# ssr.net
KiCad netlist of a schematic drawn in EAGLE
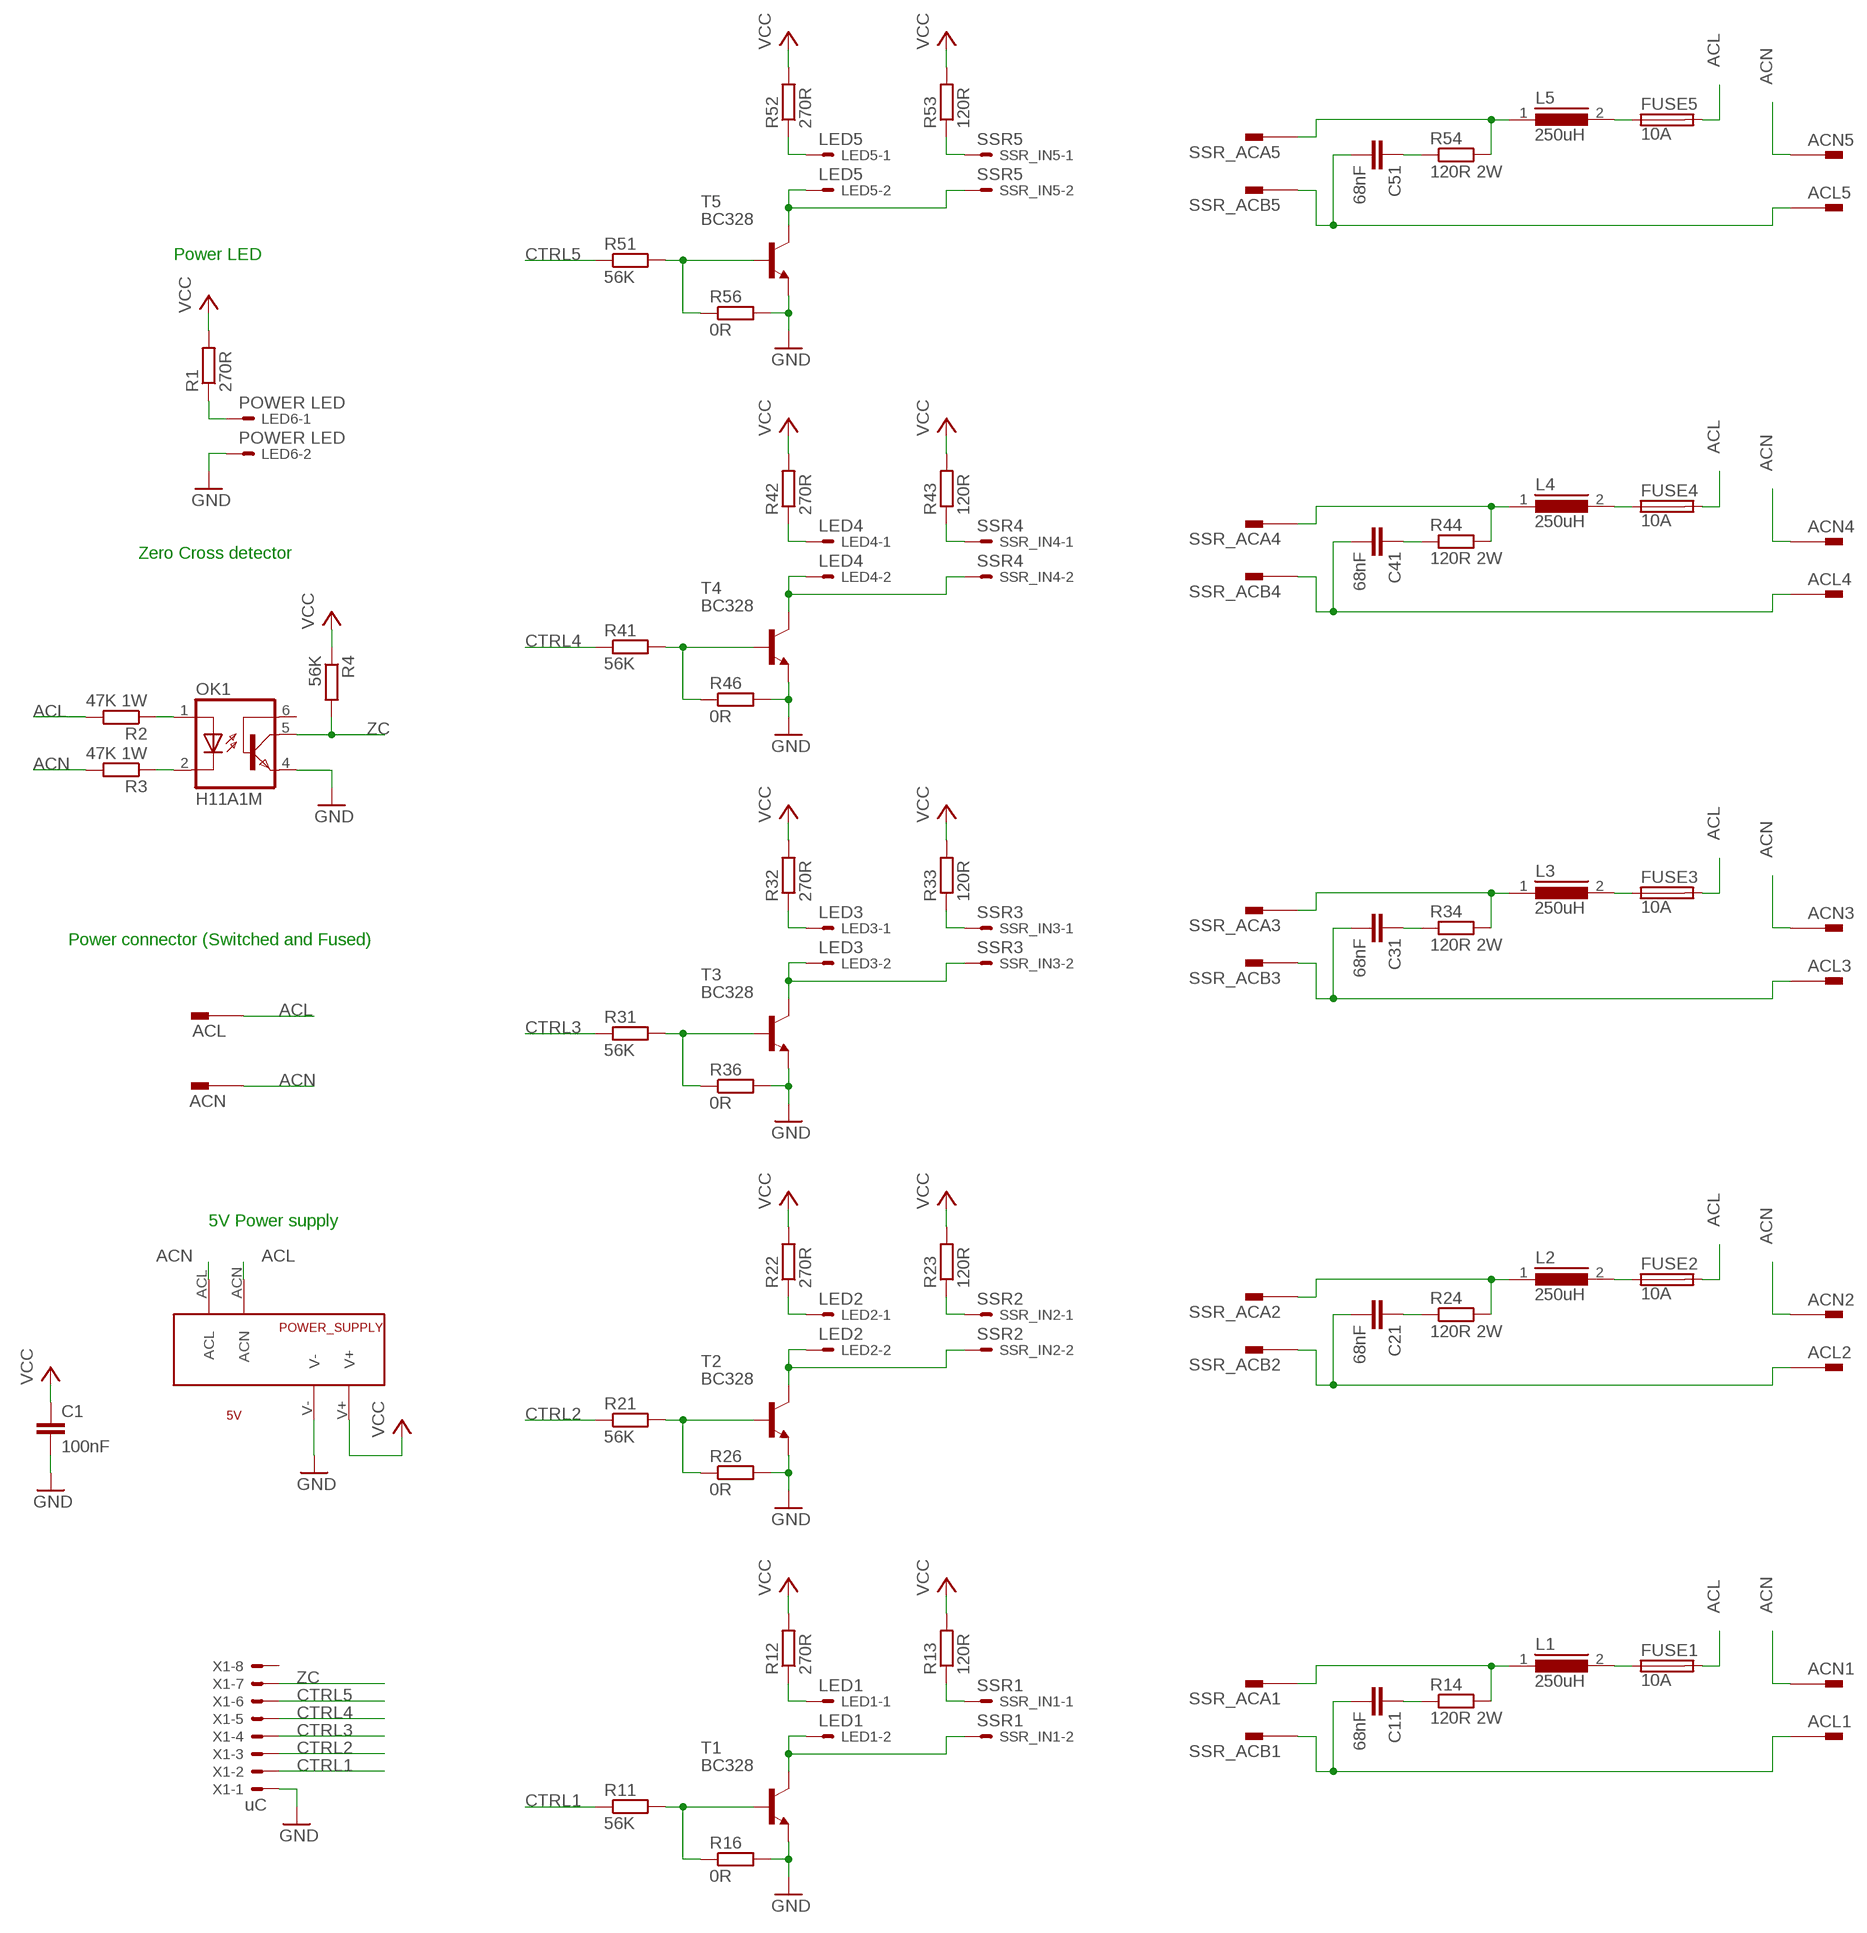
[diagram p0: schematic, sheet 1]

(export (version "E")
  (design (tool "Eeschema 10.0.6"))
  (components
    (comp (ref "ACL")
      (value "PIN2F061.080")
      (footprint "eagle-import:F061.080")
      (libsource (lib "eagle-import") (part "PIN2F061.080"))
    )
    (comp (ref "ACL1")
      (value "PIN2F061.080")
      (footprint "eagle-import:F061.080")
      (libsource (lib "eagle-import") (part "PIN2F061.080"))
    )
    (comp (ref "ACL2")
      (value "PIN2F061.080")
      (footprint "eagle-import:F061.080")
      (libsource (lib "eagle-import") (part "PIN2F061.080"))
    )
    (comp (ref "ACL3")
      (value "PIN2F061.080")
      (footprint "eagle-import:F061.080")
      (libsource (lib "eagle-import") (part "PIN2F061.080"))
    )
    (comp (ref "ACL4")
      (value "PIN2F061.080")
      (footprint "eagle-import:F061.080")
      (libsource (lib "eagle-import") (part "PIN2F061.080"))
    )
    (comp (ref "ACL5")
      (value "PIN2F061.080")
      (footprint "eagle-import:F061.080")
      (libsource (lib "eagle-import") (part "PIN2F061.080"))
    )
    (comp (ref "ACN")
      (value "PIN2F061.080")
      (footprint "eagle-import:F061.080")
      (libsource (lib "eagle-import") (part "PIN2F061.080"))
    )
    (comp (ref "ACN1")
      (value "PIN2F061.080")
      (footprint "eagle-import:F061.080")
      (libsource (lib "eagle-import") (part "PIN2F061.080"))
    )
    (comp (ref "ACN2")
      (value "PIN2F061.080")
      (footprint "eagle-import:F061.080")
      (libsource (lib "eagle-import") (part "PIN2F061.080"))
    )
    (comp (ref "ACN3")
      (value "PIN2F061.080")
      (footprint "eagle-import:F061.080")
      (libsource (lib "eagle-import") (part "PIN2F061.080"))
    )
    (comp (ref "ACN4")
      (value "PIN2F061.080")
      (footprint "eagle-import:F061.080")
      (libsource (lib "eagle-import") (part "PIN2F061.080"))
    )
    (comp (ref "ACN5")
      (value "PIN2F061.080")
      (footprint "eagle-import:F061.080")
      (libsource (lib "eagle-import") (part "PIN2F061.080"))
    )
    (comp (ref "C1")
      (value "100nF")
      (footprint "eagle-import:C2.5-2")
      (libsource (lib "eagle-import") (part "C2.5/2"))
    )
    (comp (ref "C11")
      (value "68nF")
      (footprint "eagle-import:C150-054X183")
      (libsource (lib "eagle-import") (part "C-EU150-054X183"))
    )
    (comp (ref "C21")
      (value "68nF")
      (footprint "eagle-import:C150-054X183")
      (libsource (lib "eagle-import") (part "C-EU150-054X183"))
    )
    (comp (ref "C31")
      (value "68nF")
      (footprint "eagle-import:C150-054X183")
      (libsource (lib "eagle-import") (part "C-EU150-054X183"))
    )
    (comp (ref "C41")
      (value "68nF")
      (footprint "eagle-import:C150-054X183")
      (libsource (lib "eagle-import") (part "C-EU150-054X183"))
    )
    (comp (ref "C51")
      (value "68nF")
      (footprint "eagle-import:C150-054X183")
      (libsource (lib "eagle-import") (part "C-EU150-054X183"))
    )
    (comp (ref "FUSE1")
      (value "10A")
      (footprint "eagle-import:SH22,5")
      (libsource (lib "eagle-import") (part "FUSESH22,5"))
    )
    (comp (ref "FUSE2")
      (value "10A")
      (footprint "eagle-import:SH22,5")
      (libsource (lib "eagle-import") (part "FUSESH22,5"))
    )
    (comp (ref "FUSE3")
      (value "10A")
      (footprint "eagle-import:SH22,5")
      (libsource (lib "eagle-import") (part "FUSESH22,5"))
    )
    (comp (ref "FUSE4")
      (value "10A")
      (footprint "eagle-import:SH22,5")
      (libsource (lib "eagle-import") (part "FUSESH22,5"))
    )
    (comp (ref "FUSE5")
      (value "10A")
      (footprint "eagle-import:SH22,5")
      (libsource (lib "eagle-import") (part "FUSESH22,5"))
    )
    (comp (ref "L1")
      (value "250uH")
      (footprint "eagle-import:ATCA-08")
      (libsource (lib "eagle-import") (part "ATCA-08"))
    )
    (comp (ref "L2")
      (value "250uH")
      (footprint "eagle-import:ATCA-08")
      (libsource (lib "eagle-import") (part "ATCA-08"))
    )
    (comp (ref "L3")
      (value "250uH")
      (footprint "eagle-import:ATCA-08")
      (libsource (lib "eagle-import") (part "ATCA-08"))
    )
    (comp (ref "L4")
      (value "250uH")
      (footprint "eagle-import:ATCA-08")
      (libsource (lib "eagle-import") (part "ATCA-08"))
    )
    (comp (ref "L5")
      (value "250uH")
      (footprint "eagle-import:ATCA-08")
      (libsource (lib "eagle-import") (part "ATCA-08"))
    )
    (comp (ref "LED1")
      (value "LED1")
      (footprint "eagle-import:KK-156-2")
      (libsource (lib "eagle-import") (part "KK-156-2"))
    )
    (comp (ref "LED2")
      (value "LED2")
      (footprint "eagle-import:KK-156-2")
      (libsource (lib "eagle-import") (part "KK-156-2"))
    )
    (comp (ref "LED3")
      (value "LED3")
      (footprint "eagle-import:KK-156-2")
      (libsource (lib "eagle-import") (part "KK-156-2"))
    )
    (comp (ref "LED4")
      (value "LED4")
      (footprint "eagle-import:KK-156-2")
      (libsource (lib "eagle-import") (part "KK-156-2"))
    )
    (comp (ref "LED5")
      (value "LED5")
      (footprint "eagle-import:KK-156-2")
      (libsource (lib "eagle-import") (part "KK-156-2"))
    )
    (comp (ref "LED6")
      (value "POWER LED")
      (footprint "eagle-import:KK-156-2")
      (libsource (lib "eagle-import") (part "KK-156-2"))
    )
    (comp (ref "OK1")
      (value "H11A1M")
      (footprint "eagle-import:DIL06")
      (fields (field (name "MPN") "H11A1-M"))
      (libsource (lib "eagle-import") (part "H11A?M1"))
    )
    (comp (ref "POWER_SUPPLY")
      (value "5V")
      (footprint "eagle-import:SPN00205")
      (libsource (lib "eagle-import") (part "SPN00205"))
    )
    (comp (ref "R1")
      (value "270R")
      (footprint "eagle-import:0207_10")
      (libsource (lib "eagle-import") (part "R-EU_0207/10"))
    )
    (comp (ref "R2")
      (value "47K 1W")
      (footprint "eagle-import:0309_12")
      (libsource (lib "eagle-import") (part "resistor_R-EU_0309/12"))
    )
    (comp (ref "R3")
      (value "47K 1W")
      (footprint "eagle-import:0309_12")
      (libsource (lib "eagle-import") (part "resistor_R-EU_0309/12"))
    )
    (comp (ref "R4")
      (value "56K")
      (footprint "eagle-import:0207_10")
      (libsource (lib "eagle-import") (part "R-EU_0207/10"))
    )
    (comp (ref "R11")
      (value "56K")
      (footprint "eagle-import:0207_10")
      (libsource (lib "eagle-import") (part "R-EU_0207/10"))
    )
    (comp (ref "R12")
      (value "270R")
      (footprint "eagle-import:0207_10")
      (libsource (lib "eagle-import") (part "R-EU_0207/10"))
    )
    (comp (ref "R13")
      (value "120R")
      (footprint "eagle-import:0207_10")
      (libsource (lib "eagle-import") (part "R-EU_0207/10"))
    )
    (comp (ref "R14")
      (value "120R 2W")
      (footprint "eagle-import:0617_22")
      (libsource (lib "eagle-import") (part "resistor_R-EU_0617/22"))
    )
    (comp (ref "R16")
      (value "0R")
      (footprint "eagle-import:0207_10")
      (libsource (lib "eagle-import") (part "R-EU_0207/10"))
    )
    (comp (ref "R21")
      (value "56K")
      (footprint "eagle-import:0207_10")
      (libsource (lib "eagle-import") (part "R-EU_0207/10"))
    )
    (comp (ref "R22")
      (value "270R")
      (footprint "eagle-import:0207_10")
      (libsource (lib "eagle-import") (part "R-EU_0207/10"))
    )
    (comp (ref "R23")
      (value "120R")
      (footprint "eagle-import:0207_10")
      (libsource (lib "eagle-import") (part "R-EU_0207/10"))
    )
    (comp (ref "R24")
      (value "120R 2W")
      (footprint "eagle-import:0617_22")
      (libsource (lib "eagle-import") (part "resistor_R-EU_0617/22"))
    )
    (comp (ref "R26")
      (value "0R")
      (footprint "eagle-import:0207_10")
      (libsource (lib "eagle-import") (part "R-EU_0207/10"))
    )
    (comp (ref "R31")
      (value "56K")
      (footprint "eagle-import:0207_10")
      (libsource (lib "eagle-import") (part "R-EU_0207/10"))
    )
    (comp (ref "R32")
      (value "270R")
      (footprint "eagle-import:0207_10")
      (libsource (lib "eagle-import") (part "R-EU_0207/10"))
    )
    (comp (ref "R33")
      (value "120R")
      (footprint "eagle-import:0207_10")
      (libsource (lib "eagle-import") (part "R-EU_0207/10"))
    )
    (comp (ref "R34")
      (value "120R 2W")
      (footprint "eagle-import:0617_22")
      (libsource (lib "eagle-import") (part "resistor_R-EU_0617/22"))
    )
    (comp (ref "R36")
      (value "0R")
      (footprint "eagle-import:0207_10")
      (libsource (lib "eagle-import") (part "R-EU_0207/10"))
    )
    (comp (ref "R41")
      (value "56K")
      (footprint "eagle-import:0207_10")
      (libsource (lib "eagle-import") (part "R-EU_0207/10"))
    )
    (comp (ref "R42")
      (value "270R")
      (footprint "eagle-import:0207_10")
      (libsource (lib "eagle-import") (part "R-EU_0207/10"))
    )
    (comp (ref "R43")
      (value "120R")
      (footprint "eagle-import:0207_10")
      (libsource (lib "eagle-import") (part "R-EU_0207/10"))
    )
    (comp (ref "R44")
      (value "120R 2W")
      (footprint "eagle-import:0617_22")
      (libsource (lib "eagle-import") (part "resistor_R-EU_0617/22"))
    )
    (comp (ref "R46")
      (value "0R")
      (footprint "eagle-import:0207_10")
      (libsource (lib "eagle-import") (part "R-EU_0207/10"))
    )
    (comp (ref "R51")
      (value "56K")
      (footprint "eagle-import:0207_10")
      (libsource (lib "eagle-import") (part "R-EU_0207/10"))
    )
    (comp (ref "R52")
      (value "270R")
      (footprint "eagle-import:0207_10")
      (libsource (lib "eagle-import") (part "R-EU_0207/10"))
    )
    (comp (ref "R53")
      (value "120R")
      (footprint "eagle-import:0207_10")
      (libsource (lib "eagle-import") (part "R-EU_0207/10"))
    )
    (comp (ref "R54")
      (value "120R 2W")
      (footprint "eagle-import:0617_22")
      (libsource (lib "eagle-import") (part "resistor_R-EU_0617/22"))
    )
    (comp (ref "R56")
      (value "0R")
      (footprint "eagle-import:0207_10")
      (libsource (lib "eagle-import") (part "R-EU_0207/10"))
    )
    (comp (ref "SSR_ACA1")
      (value "PIN2F061.080")
      (footprint "eagle-import:F061.080")
      (libsource (lib "eagle-import") (part "PIN2F061.080"))
    )
    (comp (ref "SSR_ACA2")
      (value "PIN2F061.080")
      (footprint "eagle-import:F061.080")
      (libsource (lib "eagle-import") (part "PIN2F061.080"))
    )
    (comp (ref "SSR_ACA3")
      (value "PIN2F061.080")
      (footprint "eagle-import:F061.080")
      (libsource (lib "eagle-import") (part "PIN2F061.080"))
    )
    (comp (ref "SSR_ACA4")
      (value "PIN2F061.080")
      (footprint "eagle-import:F061.080")
      (libsource (lib "eagle-import") (part "PIN2F061.080"))
    )
    (comp (ref "SSR_ACA5")
      (value "PIN2F061.080")
      (footprint "eagle-import:F061.080")
      (libsource (lib "eagle-import") (part "PIN2F061.080"))
    )
    (comp (ref "SSR_ACB1")
      (value "PIN2F061.080")
      (footprint "eagle-import:F061.080")
      (libsource (lib "eagle-import") (part "PIN2F061.080"))
    )
    (comp (ref "SSR_ACB2")
      (value "PIN2F061.080")
      (footprint "eagle-import:F061.080")
      (libsource (lib "eagle-import") (part "PIN2F061.080"))
    )
    (comp (ref "SSR_ACB3")
      (value "PIN2F061.080")
      (footprint "eagle-import:F061.080")
      (libsource (lib "eagle-import") (part "PIN2F061.080"))
    )
    (comp (ref "SSR_ACB4")
      (value "PIN2F061.080")
      (footprint "eagle-import:F061.080")
      (libsource (lib "eagle-import") (part "PIN2F061.080"))
    )
    (comp (ref "SSR_ACB5")
      (value "PIN2F061.080")
      (footprint "eagle-import:F061.080")
      (libsource (lib "eagle-import") (part "PIN2F061.080"))
    )
    (comp (ref "SSR_IN1")
      (value "SSR1")
      (footprint "eagle-import:KK-156-2")
      (libsource (lib "eagle-import") (part "KK-156-2"))
    )
    (comp (ref "SSR_IN2")
      (value "SSR2")
      (footprint "eagle-import:KK-156-2")
      (libsource (lib "eagle-import") (part "KK-156-2"))
    )
    (comp (ref "SSR_IN3")
      (value "SSR3")
      (footprint "eagle-import:KK-156-2")
      (libsource (lib "eagle-import") (part "KK-156-2"))
    )
    (comp (ref "SSR_IN4")
      (value "SSR4")
      (footprint "eagle-import:KK-156-2")
      (libsource (lib "eagle-import") (part "KK-156-2"))
    )
    (comp (ref "SSR_IN5")
      (value "SSR5")
      (footprint "eagle-import:KK-156-2")
      (libsource (lib "eagle-import") (part "KK-156-2"))
    )
    (comp (ref "T1")
      (value "BC328")
      (footprint "eagle-import:TO92")
      (libsource (lib "eagle-import") (part "BC328"))
    )
    (comp (ref "T2")
      (value "BC328")
      (footprint "eagle-import:TO92")
      (libsource (lib "eagle-import") (part "BC328"))
    )
    (comp (ref "T3")
      (value "BC328")
      (footprint "eagle-import:TO92")
      (libsource (lib "eagle-import") (part "BC328"))
    )
    (comp (ref "T4")
      (value "BC328")
      (footprint "eagle-import:TO92")
      (libsource (lib "eagle-import") (part "BC328"))
    )
    (comp (ref "T5")
      (value "BC328")
      (footprint "eagle-import:TO92")
      (libsource (lib "eagle-import") (part "BC328"))
    )
    (comp (ref "X1")
      (value "uC")
      (footprint "eagle-import:KK-156-8")
      (libsource (lib "eagle-import") (part "KK-156-8"))
    )
  )
  (nets
    (net (code "1") (name "/ACL") (class "Default")
      (node (ref "ACL") (pin "1A") (pinfunction "1_1A") (pintype "passive"))
      (node (ref "ACL") (pin "1B") (pinfunction "1_1B") (pintype "passive"))
      (node (ref "FUSE1") (pin "2") (pinfunction "2_2") (pintype "passive"))
      (node (ref "FUSE2") (pin "2") (pinfunction "2_2") (pintype "passive"))
      (node (ref "FUSE3") (pin "2") (pinfunction "2_2") (pintype "passive"))
      (node (ref "FUSE4") (pin "2") (pinfunction "2_2") (pintype "passive"))
      (node (ref "FUSE5") (pin "2") (pinfunction "2_2") (pintype "passive"))
      (node (ref "POWER_SUPPLY") (pin "ACN") (pinfunction "ACN_ACN") (pintype "input"))
      (node (ref "R2") (pin "2") (pinfunction "2_2") (pintype "passive"))
    )
    (net (code "2") (name "/ACN") (class "Default")
      (node (ref "ACN") (pin "1A") (pinfunction "1_1A") (pintype "passive"))
      (node (ref "ACN") (pin "1B") (pinfunction "1_1B") (pintype "passive"))
      (node (ref "ACN1") (pin "1A") (pinfunction "1_1A") (pintype "passive"))
      (node (ref "ACN1") (pin "1B") (pinfunction "1_1B") (pintype "passive"))
      (node (ref "ACN2") (pin "1A") (pinfunction "1_1A") (pintype "passive"))
      (node (ref "ACN2") (pin "1B") (pinfunction "1_1B") (pintype "passive"))
      (node (ref "ACN3") (pin "1A") (pinfunction "1_1A") (pintype "passive"))
      (node (ref "ACN3") (pin "1B") (pinfunction "1_1B") (pintype "passive"))
      (node (ref "ACN4") (pin "1A") (pinfunction "1_1A") (pintype "passive"))
      (node (ref "ACN4") (pin "1B") (pinfunction "1_1B") (pintype "passive"))
      (node (ref "ACN5") (pin "1A") (pinfunction "1_1A") (pintype "passive"))
      (node (ref "ACN5") (pin "1B") (pinfunction "1_1B") (pintype "passive"))
      (node (ref "POWER_SUPPLY") (pin "ACL") (pinfunction "ACL_ACL") (pintype "input"))
      (node (ref "R3") (pin "2") (pinfunction "2_2") (pintype "passive"))
    )
    (net (code "3") (name "/CTRL1") (class "Default")
      (node (ref "R11") (pin "1") (pinfunction "1_1") (pintype "passive"))
      (node (ref "X1") (pin "2") (pinfunction "S_2") (pintype "passive"))
    )
    (net (code "4") (name "/CTRL2") (class "Default")
      (node (ref "R21") (pin "1") (pinfunction "1_1") (pintype "passive"))
      (node (ref "X1") (pin "3") (pinfunction "S_3") (pintype "passive"))
    )
    (net (code "5") (name "/CTRL3") (class "Default")
      (node (ref "R31") (pin "1") (pinfunction "1_1") (pintype "passive"))
      (node (ref "X1") (pin "4") (pinfunction "S_4") (pintype "passive"))
    )
    (net (code "6") (name "/CTRL4") (class "Default")
      (node (ref "R41") (pin "1") (pinfunction "1_1") (pintype "passive"))
      (node (ref "X1") (pin "5") (pinfunction "S_5") (pintype "passive"))
    )
    (net (code "7") (name "/CTRL5") (class "Default")
      (node (ref "R51") (pin "1") (pinfunction "1_1") (pintype "passive"))
      (node (ref "X1") (pin "6") (pinfunction "S_6") (pintype "passive"))
    )
    (net (code "8") (name "/ZC") (class "Default")
      (node (ref "OK1") (pin "5") (pinfunction "COL_5") (pintype "passive"))
      (node (ref "R4") (pin "2") (pinfunction "2_2") (pintype "passive"))
      (node (ref "X1") (pin "7") (pinfunction "S_7") (pintype "passive"))
    )
    (net (code "9") (name "GND") (class "Default")
      (node (ref "C1") (pin "2") (pinfunction "2_2") (pintype "passive"))
      (node (ref "LED6") (pin "2") (pinfunction "S_2") (pintype "passive"))
      (node (ref "OK1") (pin "4") (pinfunction "EMI_4") (pintype "passive"))
      (node (ref "POWER_SUPPLY") (pin "V-") (pinfunction "V-_V-") (pintype "bidirectional"))
      (node (ref "R16") (pin "2") (pinfunction "2_2") (pintype "passive"))
      (node (ref "R26") (pin "2") (pinfunction "2_2") (pintype "passive"))
      (node (ref "R36") (pin "2") (pinfunction "2_2") (pintype "passive"))
      (node (ref "R46") (pin "2") (pinfunction "2_2") (pintype "passive"))
      (node (ref "R56") (pin "2") (pinfunction "2_2") (pintype "passive"))
      (node (ref "T1") (pin "1") (pinfunction "E_1") (pintype "passive"))
      (node (ref "T2") (pin "1") (pinfunction "E_1") (pintype "passive"))
      (node (ref "T3") (pin "1") (pinfunction "E_1") (pintype "passive"))
      (node (ref "T4") (pin "1") (pinfunction "E_1") (pintype "passive"))
      (node (ref "T5") (pin "1") (pinfunction "E_1") (pintype "passive"))
      (node (ref "X1") (pin "1") (pinfunction "S_1") (pintype "passive"))
    )
    (net (code "10") (name "Net-(ACL1-1-Pad1A)") (class "Default")
      (node (ref "ACL1") (pin "1A") (pinfunction "1_1A") (pintype "passive"))
      (node (ref "ACL1") (pin "1B") (pinfunction "1_1B") (pintype "passive"))
      (node (ref "C11") (pin "2") (pinfunction "2_2") (pintype "passive"))
      (node (ref "SSR_ACB1") (pin "1A") (pinfunction "1_1A") (pintype "passive"))
      (node (ref "SSR_ACB1") (pin "1B") (pinfunction "1_1B") (pintype "passive"))
    )
    (net (code "11") (name "Net-(ACL2-1-Pad1A)") (class "Default")
      (node (ref "ACL2") (pin "1A") (pinfunction "1_1A") (pintype "passive"))
      (node (ref "ACL2") (pin "1B") (pinfunction "1_1B") (pintype "passive"))
      (node (ref "C21") (pin "2") (pinfunction "2_2") (pintype "passive"))
      (node (ref "SSR_ACB2") (pin "1A") (pinfunction "1_1A") (pintype "passive"))
      (node (ref "SSR_ACB2") (pin "1B") (pinfunction "1_1B") (pintype "passive"))
    )
    (net (code "12") (name "Net-(ACL3-1-Pad1A)") (class "Default")
      (node (ref "ACL3") (pin "1A") (pinfunction "1_1A") (pintype "passive"))
      (node (ref "ACL3") (pin "1B") (pinfunction "1_1B") (pintype "passive"))
      (node (ref "C31") (pin "2") (pinfunction "2_2") (pintype "passive"))
      (node (ref "SSR_ACB3") (pin "1A") (pinfunction "1_1A") (pintype "passive"))
      (node (ref "SSR_ACB3") (pin "1B") (pinfunction "1_1B") (pintype "passive"))
    )
    (net (code "13") (name "Net-(ACL4-1-Pad1A)") (class "Default")
      (node (ref "ACL4") (pin "1A") (pinfunction "1_1A") (pintype "passive"))
      (node (ref "ACL4") (pin "1B") (pinfunction "1_1B") (pintype "passive"))
      (node (ref "C41") (pin "2") (pinfunction "2_2") (pintype "passive"))
      (node (ref "SSR_ACB4") (pin "1A") (pinfunction "1_1A") (pintype "passive"))
      (node (ref "SSR_ACB4") (pin "1B") (pinfunction "1_1B") (pintype "passive"))
    )
    (net (code "14") (name "Net-(ACL5-1-Pad1A)") (class "Default")
      (node (ref "ACL5") (pin "1A") (pinfunction "1_1A") (pintype "passive"))
      (node (ref "ACL5") (pin "1B") (pinfunction "1_1B") (pintype "passive"))
      (node (ref "C51") (pin "2") (pinfunction "2_2") (pintype "passive"))
      (node (ref "SSR_ACB5") (pin "1A") (pinfunction "1_1A") (pintype "passive"))
      (node (ref "SSR_ACB5") (pin "1B") (pinfunction "1_1B") (pintype "passive"))
    )
    (net (code "15") (name "Net-(C11-Pad1)") (class "Default")
      (node (ref "C11") (pin "1") (pinfunction "1_1") (pintype "passive"))
      (node (ref "R14") (pin "1") (pinfunction "1_1") (pintype "passive"))
    )
    (net (code "16") (name "Net-(C21-Pad1)") (class "Default")
      (node (ref "C21") (pin "1") (pinfunction "1_1") (pintype "passive"))
      (node (ref "R24") (pin "1") (pinfunction "1_1") (pintype "passive"))
    )
    (net (code "17") (name "Net-(C31-Pad1)") (class "Default")
      (node (ref "C31") (pin "1") (pinfunction "1_1") (pintype "passive"))
      (node (ref "R34") (pin "1") (pinfunction "1_1") (pintype "passive"))
    )
    (net (code "18") (name "Net-(C41-Pad1)") (class "Default")
      (node (ref "C41") (pin "1") (pinfunction "1_1") (pintype "passive"))
      (node (ref "R44") (pin "1") (pinfunction "1_1") (pintype "passive"))
    )
    (net (code "19") (name "Net-(C51-Pad1)") (class "Default")
      (node (ref "C51") (pin "1") (pinfunction "1_1") (pintype "passive"))
      (node (ref "R54") (pin "1") (pinfunction "1_1") (pintype "passive"))
    )
    (net (code "20") (name "Net-(FUSE1-Pad1)") (class "Default")
      (node (ref "FUSE1") (pin "1") (pinfunction "1_1") (pintype "passive"))
      (node (ref "L1") (pin "2") (pinfunction "2_2") (pintype "passive"))
    )
    (net (code "21") (name "Net-(FUSE2-Pad1)") (class "Default")
      (node (ref "FUSE2") (pin "1") (pinfunction "1_1") (pintype "passive"))
      (node (ref "L2") (pin "2") (pinfunction "2_2") (pintype "passive"))
    )
    (net (code "22") (name "Net-(FUSE3-Pad1)") (class "Default")
      (node (ref "FUSE3") (pin "1") (pinfunction "1_1") (pintype "passive"))
      (node (ref "L3") (pin "2") (pinfunction "2_2") (pintype "passive"))
    )
    (net (code "23") (name "Net-(FUSE4-Pad1)") (class "Default")
      (node (ref "FUSE4") (pin "1") (pinfunction "1_1") (pintype "passive"))
      (node (ref "L4") (pin "2") (pinfunction "2_2") (pintype "passive"))
    )
    (net (code "24") (name "Net-(FUSE5-Pad1)") (class "Default")
      (node (ref "FUSE5") (pin "1") (pinfunction "1_1") (pintype "passive"))
      (node (ref "L5") (pin "2") (pinfunction "2_2") (pintype "passive"))
    )
    (net (code "25") (name "Net-(L1-Pad1)") (class "Default")
      (node (ref "L1") (pin "1") (pinfunction "1_1") (pintype "passive"))
      (node (ref "R14") (pin "2") (pinfunction "2_2") (pintype "passive"))
      (node (ref "SSR_ACA1") (pin "1A") (pinfunction "1_1A") (pintype "passive"))
      (node (ref "SSR_ACA1") (pin "1B") (pinfunction "1_1B") (pintype "passive"))
    )
    (net (code "26") (name "Net-(L2-Pad1)") (class "Default")
      (node (ref "L2") (pin "1") (pinfunction "1_1") (pintype "passive"))
      (node (ref "R24") (pin "2") (pinfunction "2_2") (pintype "passive"))
      (node (ref "SSR_ACA2") (pin "1A") (pinfunction "1_1A") (pintype "passive"))
      (node (ref "SSR_ACA2") (pin "1B") (pinfunction "1_1B") (pintype "passive"))
    )
    (net (code "27") (name "Net-(L3-Pad1)") (class "Default")
      (node (ref "L3") (pin "1") (pinfunction "1_1") (pintype "passive"))
      (node (ref "R34") (pin "2") (pinfunction "2_2") (pintype "passive"))
      (node (ref "SSR_ACA3") (pin "1A") (pinfunction "1_1A") (pintype "passive"))
      (node (ref "SSR_ACA3") (pin "1B") (pinfunction "1_1B") (pintype "passive"))
    )
    (net (code "28") (name "Net-(L4-Pad1)") (class "Default")
      (node (ref "L4") (pin "1") (pinfunction "1_1") (pintype "passive"))
      (node (ref "R44") (pin "2") (pinfunction "2_2") (pintype "passive"))
      (node (ref "SSR_ACA4") (pin "1A") (pinfunction "1_1A") (pintype "passive"))
      (node (ref "SSR_ACA4") (pin "1B") (pinfunction "1_1B") (pintype "passive"))
    )
    (net (code "29") (name "Net-(L5-Pad1)") (class "Default")
      (node (ref "L5") (pin "1") (pinfunction "1_1") (pintype "passive"))
      (node (ref "R54") (pin "2") (pinfunction "2_2") (pintype "passive"))
      (node (ref "SSR_ACA5") (pin "1A") (pinfunction "1_1A") (pintype "passive"))
      (node (ref "SSR_ACA5") (pin "1B") (pinfunction "1_1B") (pintype "passive"))
    )
    (net (code "30") (name "Net-(LED1A-S)") (class "Default")
      (node (ref "LED1") (pin "1") (pinfunction "S_1") (pintype "passive"))
      (node (ref "R12") (pin "1") (pinfunction "1_1") (pintype "passive"))
    )
    (net (code "31") (name "Net-(LED1B-S)") (class "Default")
      (node (ref "LED1") (pin "2") (pinfunction "S_2") (pintype "passive"))
      (node (ref "SSR_IN1") (pin "2") (pinfunction "S_2") (pintype "passive"))
      (node (ref "T1") (pin "3") (pinfunction "C_3") (pintype "passive"))
    )
    (net (code "32") (name "Net-(LED2A-S)") (class "Default")
      (node (ref "LED2") (pin "1") (pinfunction "S_1") (pintype "passive"))
      (node (ref "R22") (pin "1") (pinfunction "1_1") (pintype "passive"))
    )
    (net (code "33") (name "Net-(LED2B-S)") (class "Default")
      (node (ref "LED2") (pin "2") (pinfunction "S_2") (pintype "passive"))
      (node (ref "SSR_IN2") (pin "2") (pinfunction "S_2") (pintype "passive"))
      (node (ref "T2") (pin "3") (pinfunction "C_3") (pintype "passive"))
    )
    (net (code "34") (name "Net-(LED3A-S)") (class "Default")
      (node (ref "LED3") (pin "1") (pinfunction "S_1") (pintype "passive"))
      (node (ref "R32") (pin "1") (pinfunction "1_1") (pintype "passive"))
    )
    (net (code "35") (name "Net-(LED3B-S)") (class "Default")
      (node (ref "LED3") (pin "2") (pinfunction "S_2") (pintype "passive"))
      (node (ref "SSR_IN3") (pin "2") (pinfunction "S_2") (pintype "passive"))
      (node (ref "T3") (pin "3") (pinfunction "C_3") (pintype "passive"))
    )
    (net (code "36") (name "Net-(LED4A-S)") (class "Default")
      (node (ref "LED4") (pin "1") (pinfunction "S_1") (pintype "passive"))
      (node (ref "R42") (pin "1") (pinfunction "1_1") (pintype "passive"))
    )
    (net (code "37") (name "Net-(LED4B-S)") (class "Default")
      (node (ref "LED4") (pin "2") (pinfunction "S_2") (pintype "passive"))
      (node (ref "SSR_IN4") (pin "2") (pinfunction "S_2") (pintype "passive"))
      (node (ref "T4") (pin "3") (pinfunction "C_3") (pintype "passive"))
    )
    (net (code "38") (name "Net-(LED5A-S)") (class "Default")
      (node (ref "LED5") (pin "1") (pinfunction "S_1") (pintype "passive"))
      (node (ref "R52") (pin "1") (pinfunction "1_1") (pintype "passive"))
    )
    (net (code "39") (name "Net-(LED5B-S)") (class "Default")
      (node (ref "LED5") (pin "2") (pinfunction "S_2") (pintype "passive"))
      (node (ref "SSR_IN5") (pin "2") (pinfunction "S_2") (pintype "passive"))
      (node (ref "T5") (pin "3") (pinfunction "C_3") (pintype "passive"))
    )
    (net (code "40") (name "Net-(LED6A-S)") (class "Default")
      (node (ref "LED6") (pin "1") (pinfunction "S_1") (pintype "passive"))
      (node (ref "R1") (pin "1") (pinfunction "1_1") (pintype "passive"))
    )
    (net (code "41") (name "Net-(OK1-A)") (class "Default")
      (node (ref "OK1") (pin "1") (pinfunction "A_1") (pintype "passive"))
      (node (ref "R2") (pin "1") (pinfunction "1_1") (pintype "passive"))
    )
    (net (code "42") (name "Net-(OK1-C)") (class "Default")
      (node (ref "OK1") (pin "2") (pinfunction "C_2") (pintype "passive"))
      (node (ref "R3") (pin "1") (pinfunction "1_1") (pintype "passive"))
    )
    (net (code "43") (name "Net-(SSR_IN1A-S)") (class "Default")
      (node (ref "R13") (pin "1") (pinfunction "1_1") (pintype "passive"))
      (node (ref "SSR_IN1") (pin "1") (pinfunction "S_1") (pintype "passive"))
    )
    (net (code "44") (name "Net-(SSR_IN2A-S)") (class "Default")
      (node (ref "R23") (pin "1") (pinfunction "1_1") (pintype "passive"))
      (node (ref "SSR_IN2") (pin "1") (pinfunction "S_1") (pintype "passive"))
    )
    (net (code "45") (name "Net-(SSR_IN3A-S)") (class "Default")
      (node (ref "R33") (pin "1") (pinfunction "1_1") (pintype "passive"))
      (node (ref "SSR_IN3") (pin "1") (pinfunction "S_1") (pintype "passive"))
    )
    (net (code "46") (name "Net-(SSR_IN4A-S)") (class "Default")
      (node (ref "R43") (pin "1") (pinfunction "1_1") (pintype "passive"))
      (node (ref "SSR_IN4") (pin "1") (pinfunction "S_1") (pintype "passive"))
    )
    (net (code "47") (name "Net-(SSR_IN5A-S)") (class "Default")
      (node (ref "R53") (pin "1") (pinfunction "1_1") (pintype "passive"))
      (node (ref "SSR_IN5") (pin "1") (pinfunction "S_1") (pintype "passive"))
    )
    (net (code "48") (name "Net-(T1-B)") (class "Default")
      (node (ref "R11") (pin "2") (pinfunction "2_2") (pintype "passive"))
      (node (ref "R16") (pin "1") (pinfunction "1_1") (pintype "passive"))
      (node (ref "T1") (pin "2") (pinfunction "B_2") (pintype "passive"))
    )
    (net (code "49") (name "Net-(T2-B)") (class "Default")
      (node (ref "R21") (pin "2") (pinfunction "2_2") (pintype "passive"))
      (node (ref "R26") (pin "1") (pinfunction "1_1") (pintype "passive"))
      (node (ref "T2") (pin "2") (pinfunction "B_2") (pintype "passive"))
    )
    (net (code "50") (name "Net-(T3-B)") (class "Default")
      (node (ref "R31") (pin "2") (pinfunction "2_2") (pintype "passive"))
      (node (ref "R36") (pin "1") (pinfunction "1_1") (pintype "passive"))
      (node (ref "T3") (pin "2") (pinfunction "B_2") (pintype "passive"))
    )
    (net (code "51") (name "Net-(T4-B)") (class "Default")
      (node (ref "R41") (pin "2") (pinfunction "2_2") (pintype "passive"))
      (node (ref "R46") (pin "1") (pinfunction "1_1") (pintype "passive"))
      (node (ref "T4") (pin "2") (pinfunction "B_2") (pintype "passive"))
    )
    (net (code "52") (name "Net-(T5-B)") (class "Default")
      (node (ref "R51") (pin "2") (pinfunction "2_2") (pintype "passive"))
      (node (ref "R56") (pin "1") (pinfunction "1_1") (pintype "passive"))
      (node (ref "T5") (pin "2") (pinfunction "B_2") (pintype "passive"))
    )
    (net (code "53") (name "VCC") (class "Default")
      (node (ref "C1") (pin "1") (pinfunction "1_1") (pintype "passive"))
      (node (ref "POWER_SUPPLY") (pin "V+") (pinfunction "V+_V+") (pintype "power_in"))
      (node (ref "R1") (pin "2") (pinfunction "2_2") (pintype "passive"))
      (node (ref "R12") (pin "2") (pinfunction "2_2") (pintype "passive"))
      (node (ref "R13") (pin "2") (pinfunction "2_2") (pintype "passive"))
      (node (ref "R22") (pin "2") (pinfunction "2_2") (pintype "passive"))
      (node (ref "R23") (pin "2") (pinfunction "2_2") (pintype "passive"))
      (node (ref "R32") (pin "2") (pinfunction "2_2") (pintype "passive"))
      (node (ref "R33") (pin "2") (pinfunction "2_2") (pintype "passive"))
      (node (ref "R4") (pin "1") (pinfunction "1_1") (pintype "passive"))
      (node (ref "R42") (pin "2") (pinfunction "2_2") (pintype "passive"))
      (node (ref "R43") (pin "2") (pinfunction "2_2") (pintype "passive"))
      (node (ref "R52") (pin "2") (pinfunction "2_2") (pintype "passive"))
      (node (ref "R53") (pin "2") (pinfunction "2_2") (pintype "passive"))
    )
    (net (code "54") (name "unconnected-(OK1-BAS-Pad6)") (class "Default")
      (node (ref "OK1") (pin "6") (pinfunction "BAS_6") (pintype "passive"))
    )
    (net (code "55") (name "unconnected-(X1H-S-Pad8)") (class "Default")
      (node (ref "X1") (pin "8") (pinfunction "S_8") (pintype "passive"))
    )
  )
)
